# 7seg.net
KiCad netlist of a schematic drawn in EAGLE
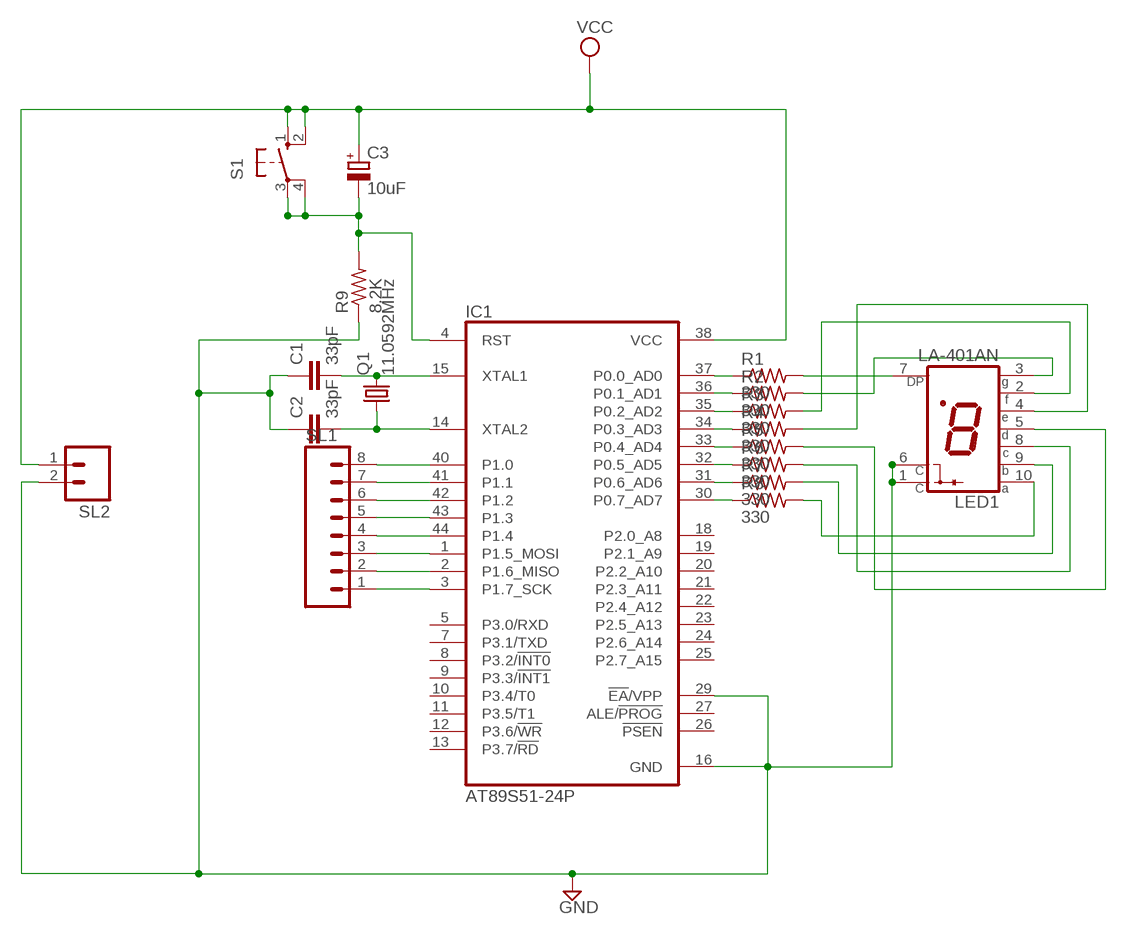
[diagram p0: schematic, sheet 1]

(export (version "E")
  (design (tool "Eeschema 10.0.6"))
  (components
    (comp (ref "C1")
      (value "33pF")
      (footprint "eagle-import:C1206K")
      (libsource (lib "eagle-import") (part "C-EUC1206K"))
    )
    (comp (ref "C2")
      (value "33pF")
      (footprint "eagle-import:C1206K")
      (libsource (lib "eagle-import") (part "C-EUC1206K"))
    )
    (comp (ref "C3")
      (value "10uF")
      (footprint "eagle-import:140CLH-1010")
      (libsource (lib "eagle-import") (part "CPOL-EU140CLH-1010"))
    )
    (comp (ref "IC1")
      (value "AT89S51-24P")
      (footprint "eagle-import:TQFP44")
      (libsource (lib "eagle-import") (part "AT89S51P-24"))
    )
    (comp (ref "LED1")
      (value "LA-401AN")
      (footprint "eagle-import:LA-401")
      (libsource (lib "eagle-import") (part "LA-401NA"))
    )
    (comp (ref "Q1")
      (value "11.0592MHz")
      (footprint "eagle-import:TC26V")
      (libsource (lib "eagle-import") (part "CRYSTALTC26V"))
    )
    (comp (ref "R1")
      (value "330")
      (footprint "eagle-import:M1206")
      (libsource (lib "eagle-import") (part "R-US_M1206"))
    )
    (comp (ref "R2")
      (value "330")
      (footprint "eagle-import:M1206")
      (libsource (lib "eagle-import") (part "R-US_M1206"))
    )
    (comp (ref "R3")
      (value "330")
      (footprint "eagle-import:M1206")
      (libsource (lib "eagle-import") (part "R-US_M1206"))
    )
    (comp (ref "R4")
      (value "330")
      (footprint "eagle-import:M1206")
      (libsource (lib "eagle-import") (part "R-US_M1206"))
    )
    (comp (ref "R5")
      (value "330")
      (footprint "eagle-import:M1206")
      (libsource (lib "eagle-import") (part "R-US_M1206"))
    )
    (comp (ref "R6")
      (value "330")
      (footprint "eagle-import:M1206")
      (libsource (lib "eagle-import") (part "R-US_M1206"))
    )
    (comp (ref "R7")
      (value "330")
      (footprint "eagle-import:M1206")
      (libsource (lib "eagle-import") (part "R-US_M1206"))
    )
    (comp (ref "R8")
      (value "330")
      (footprint "eagle-import:M1206")
      (libsource (lib "eagle-import") (part "R-US_M1206"))
    )
    (comp (ref "R9")
      (value "8.2K")
      (footprint "eagle-import:M1206")
      (libsource (lib "eagle-import") (part "R-US_M1206"))
    )
    (comp (ref "S1")
      (value "10-XX")
      (footprint "eagle-import:B3F-10XX")
      (fields (field (name "MPN") "B3F-1000"))
      (libsource (lib "eagle-import") (part "10-XX"))
    )
    (comp (ref "SL1")
      (value "MA08")
      (footprint "eagle-import:08PA")
      (libsource (lib "eagle-import") (part "MA08"))
    )
    (comp (ref "SL2")
      (value "MA02")
      (footprint "eagle-import:02PA")
      (libsource (lib "eagle-import") (part "MA02"))
    )
  )
  (nets
    (net (code "1") (name "GND") (class "Default")
      (node (ref "C1") (pin "1") (pinfunction "1_1") (pintype "passive"))
      (node (ref "C2") (pin "1") (pinfunction "1_1") (pintype "passive"))
      (node (ref "IC1") (pin "16") (pinfunction "GND_16") (pintype "power_in"))
      (node (ref "IC1") (pin "29") (pinfunction "~{EA}/VPP_29") (pintype "input"))
      (node (ref "LED1") (pin "1") (pinfunction "C_1") (pintype "passive"))
      (node (ref "LED1") (pin "6") (pinfunction "C_6") (pintype "passive"))
      (node (ref "R9") (pin "1") (pinfunction "1_1") (pintype "passive"))
      (node (ref "SL2") (pin "2") (pinfunction "2_2") (pintype "passive"))
    )
    (net (code "2") (name "Net-(IC1A-P0.0_AD0)") (class "Default")
      (node (ref "IC1") (pin "37") (pinfunction "P0.0_AD0_37") (pintype "bidirectional"))
      (node (ref "R1") (pin "1") (pinfunction "1_1") (pintype "passive"))
    )
    (net (code "3") (name "Net-(IC1A-P0.1_AD1)") (class "Default")
      (node (ref "IC1") (pin "36") (pinfunction "P0.1_AD1_36") (pintype "bidirectional"))
      (node (ref "R2") (pin "1") (pinfunction "1_1") (pintype "passive"))
    )
    (net (code "4") (name "Net-(IC1A-P0.2_AD2)") (class "Default")
      (node (ref "IC1") (pin "35") (pinfunction "P0.2_AD2_35") (pintype "bidirectional"))
      (node (ref "R3") (pin "1") (pinfunction "1_1") (pintype "passive"))
    )
    (net (code "5") (name "Net-(IC1A-P0.3_AD3)") (class "Default")
      (node (ref "IC1") (pin "34") (pinfunction "P0.3_AD3_34") (pintype "bidirectional"))
      (node (ref "R4") (pin "1") (pinfunction "1_1") (pintype "passive"))
    )
    (net (code "6") (name "Net-(IC1A-P0.4_AD4)") (class "Default")
      (node (ref "IC1") (pin "33") (pinfunction "P0.4_AD4_33") (pintype "bidirectional"))
      (node (ref "R5") (pin "1") (pinfunction "1_1") (pintype "passive"))
    )
    (net (code "7") (name "Net-(IC1A-P0.5_AD5)") (class "Default")
      (node (ref "IC1") (pin "32") (pinfunction "P0.5_AD5_32") (pintype "bidirectional"))
      (node (ref "R6") (pin "1") (pinfunction "1_1") (pintype "passive"))
    )
    (net (code "8") (name "Net-(IC1A-P0.6_AD6)") (class "Default")
      (node (ref "IC1") (pin "31") (pinfunction "P0.6_AD6_31") (pintype "bidirectional"))
      (node (ref "R7") (pin "1") (pinfunction "1_1") (pintype "passive"))
    )
    (net (code "9") (name "Net-(IC1A-P0.7_AD7)") (class "Default")
      (node (ref "IC1") (pin "30") (pinfunction "P0.7_AD7_30") (pintype "bidirectional"))
      (node (ref "R8") (pin "1") (pinfunction "1_1") (pintype "passive"))
    )
    (net (code "10") (name "Net-(IC1A-P1.0)") (class "Default")
      (node (ref "IC1") (pin "40") (pinfunction "P1.0_40") (pintype "bidirectional"))
      (node (ref "SL1") (pin "8") (pinfunction "8_8") (pintype "passive"))
    )
    (net (code "11") (name "Net-(IC1A-P1.1)") (class "Default")
      (node (ref "IC1") (pin "41") (pinfunction "P1.1_41") (pintype "bidirectional"))
      (node (ref "SL1") (pin "7") (pinfunction "7_7") (pintype "passive"))
    )
    (net (code "12") (name "Net-(IC1A-P1.2)") (class "Default")
      (node (ref "IC1") (pin "42") (pinfunction "P1.2_42") (pintype "bidirectional"))
      (node (ref "SL1") (pin "6") (pinfunction "6_6") (pintype "passive"))
    )
    (net (code "13") (name "Net-(IC1A-P1.3)") (class "Default")
      (node (ref "IC1") (pin "43") (pinfunction "P1.3_43") (pintype "bidirectional"))
      (node (ref "SL1") (pin "5") (pinfunction "5_5") (pintype "passive"))
    )
    (net (code "14") (name "Net-(IC1A-P1.4)") (class "Default")
      (node (ref "IC1") (pin "44") (pinfunction "P1.4_44") (pintype "bidirectional"))
      (node (ref "SL1") (pin "4") (pinfunction "4_4") (pintype "passive"))
    )
    (net (code "15") (name "Net-(IC1A-P1.5_MOSI)") (class "Default")
      (node (ref "IC1") (pin "1") (pinfunction "P1.5_MOSI_1") (pintype "bidirectional"))
      (node (ref "SL1") (pin "3") (pinfunction "3_3") (pintype "passive"))
    )
    (net (code "16") (name "Net-(IC1A-P1.6_MISO)") (class "Default")
      (node (ref "IC1") (pin "2") (pinfunction "P1.6_MISO_2") (pintype "bidirectional"))
      (node (ref "SL1") (pin "2") (pinfunction "2_2") (pintype "passive"))
    )
    (net (code "17") (name "Net-(IC1A-P1.7_SCK)") (class "Default")
      (node (ref "IC1") (pin "3") (pinfunction "P1.7_SCK_3") (pintype "bidirectional"))
      (node (ref "SL1") (pin "1") (pinfunction "1_1") (pintype "passive"))
    )
    (net (code "18") (name "Net-(IC1A-RST)") (class "Default")
      (node (ref "C3") (pin "-") (pinfunction "-_-") (pintype "passive"))
      (node (ref "IC1") (pin "4") (pinfunction "RST_4") (pintype "input"))
      (node (ref "R9") (pin "2") (pinfunction "2_2") (pintype "passive"))
      (node (ref "S1") (pin "3") (pinfunction "P_3") (pintype "passive"))
      (node (ref "S1") (pin "4") (pinfunction "P1_4") (pintype "passive"))
    )
    (net (code "19") (name "Net-(IC1A-XTAL1)") (class "Default")
      (node (ref "C1") (pin "2") (pinfunction "2_2") (pintype "passive"))
      (node (ref "IC1") (pin "15") (pinfunction "XTAL1_15") (pintype "input"))
      (node (ref "Q1") (pin "2") (pinfunction "2_2") (pintype "passive"))
    )
    (net (code "20") (name "Net-(IC1A-XTAL2)") (class "Default")
      (node (ref "C2") (pin "2") (pinfunction "2_2") (pintype "passive"))
      (node (ref "IC1") (pin "14") (pinfunction "XTAL2_14") (pintype "input"))
      (node (ref "Q1") (pin "1") (pinfunction "1_1") (pintype "passive"))
    )
    (net (code "21") (name "Net-(LED1-A)") (class "Default")
      (node (ref "LED1") (pin "10") (pinfunction "A_10") (pintype "passive"))
      (node (ref "R8") (pin "2") (pinfunction "2_2") (pintype "passive"))
    )
    (net (code "22") (name "Net-(LED1-B)") (class "Default")
      (node (ref "LED1") (pin "9") (pinfunction "B_9") (pintype "passive"))
      (node (ref "R7") (pin "2") (pinfunction "2_2") (pintype "passive"))
    )
    (net (code "23") (name "Net-(LED1-C-Pad8)") (class "Default")
      (node (ref "LED1") (pin "8") (pinfunction "C_8") (pintype "passive"))
      (node (ref "R6") (pin "2") (pinfunction "2_2") (pintype "passive"))
    )
    (net (code "24") (name "Net-(LED1-D)") (class "Default")
      (node (ref "LED1") (pin "5") (pinfunction "D_5") (pintype "passive"))
      (node (ref "R5") (pin "2") (pinfunction "2_2") (pintype "passive"))
    )
    (net (code "25") (name "Net-(LED1-DP)") (class "Default")
      (node (ref "LED1") (pin "7") (pinfunction "DP_7") (pintype "passive"))
      (node (ref "R1") (pin "2") (pinfunction "2_2") (pintype "passive"))
    )
    (net (code "26") (name "Net-(LED1-E)") (class "Default")
      (node (ref "LED1") (pin "4") (pinfunction "E_4") (pintype "passive"))
      (node (ref "R4") (pin "2") (pinfunction "2_2") (pintype "passive"))
    )
    (net (code "27") (name "Net-(LED1-F)") (class "Default")
      (node (ref "LED1") (pin "2") (pinfunction "F_2") (pintype "passive"))
      (node (ref "R3") (pin "2") (pinfunction "2_2") (pintype "passive"))
    )
    (net (code "28") (name "Net-(LED1-G)") (class "Default")
      (node (ref "LED1") (pin "3") (pinfunction "G_3") (pintype "passive"))
      (node (ref "R2") (pin "2") (pinfunction "2_2") (pintype "passive"))
    )
    (net (code "29") (name "VCC") (class "Default")
      (node (ref "C3") (pin "+") (pinfunction "+_+") (pintype "passive"))
      (node (ref "IC1") (pin "38") (pinfunction "VCC_38") (pintype "power_in"))
      (node (ref "S1") (pin "1") (pinfunction "S_1") (pintype "passive"))
      (node (ref "S1") (pin "2") (pinfunction "S1_2") (pintype "passive"))
      (node (ref "SL2") (pin "1") (pinfunction "1_1") (pintype "passive"))
    )
    (net (code "30") (name "unconnected-(IC1A-ALE{slash}~{PROG}-Pad27)") (class "Default")
      (node (ref "IC1") (pin "27") (pinfunction "ALE/~{PROG}_27") (pintype "output"))
    )
    (net (code "31") (name "unconnected-(IC1A-P2.0_A8-Pad18)") (class "Default")
      (node (ref "IC1") (pin "18") (pinfunction "P2.0_A8_18") (pintype "bidirectional"))
    )
    (net (code "32") (name "unconnected-(IC1A-P2.1_A9-Pad19)") (class "Default")
      (node (ref "IC1") (pin "19") (pinfunction "P2.1_A9_19") (pintype "bidirectional"))
    )
    (net (code "33") (name "unconnected-(IC1A-P2.2_A10-Pad20)") (class "Default")
      (node (ref "IC1") (pin "20") (pinfunction "P2.2_A10_20") (pintype "bidirectional"))
    )
    (net (code "34") (name "unconnected-(IC1A-P2.3_A11-Pad21)") (class "Default")
      (node (ref "IC1") (pin "21") (pinfunction "P2.3_A11_21") (pintype "bidirectional"))
    )
    (net (code "35") (name "unconnected-(IC1A-P2.4_A12-Pad22)") (class "Default")
      (node (ref "IC1") (pin "22") (pinfunction "P2.4_A12_22") (pintype "bidirectional"))
    )
    (net (code "36") (name "unconnected-(IC1A-P2.5_A13-Pad23)") (class "Default")
      (node (ref "IC1") (pin "23") (pinfunction "P2.5_A13_23") (pintype "bidirectional"))
    )
    (net (code "37") (name "unconnected-(IC1A-P2.6_A14-Pad24)") (class "Default")
      (node (ref "IC1") (pin "24") (pinfunction "P2.6_A14_24") (pintype "bidirectional"))
    )
    (net (code "38") (name "unconnected-(IC1A-P2.7_A15-Pad25)") (class "Default")
      (node (ref "IC1") (pin "25") (pinfunction "P2.7_A15_25") (pintype "bidirectional"))
    )
    (net (code "39") (name "unconnected-(IC1A-P3.0{slash}RXD-Pad5)") (class "Default")
      (node (ref "IC1") (pin "5") (pinfunction "P3.0/RXD_5") (pintype "bidirectional"))
    )
    (net (code "40") (name "unconnected-(IC1A-P3.1{slash}TXD-Pad7)") (class "Default")
      (node (ref "IC1") (pin "7") (pinfunction "P3.1/TXD_7") (pintype "bidirectional"))
    )
    (net (code "41") (name "unconnected-(IC1A-P3.2{slash}~{INT0}-Pad8)") (class "Default")
      (node (ref "IC1") (pin "8") (pinfunction "P3.2/~{INT0}_8") (pintype "bidirectional"))
    )
    (net (code "42") (name "unconnected-(IC1A-P3.3{slash}~{INT1}-Pad9)") (class "Default")
      (node (ref "IC1") (pin "9") (pinfunction "P3.3/~{INT1}_9") (pintype "bidirectional"))
    )
    (net (code "43") (name "unconnected-(IC1A-P3.4{slash}T0-Pad10)") (class "Default")
      (node (ref "IC1") (pin "10") (pinfunction "P3.4/T0_10") (pintype "bidirectional"))
    )
    (net (code "44") (name "unconnected-(IC1A-P3.5{slash}T1-Pad11)") (class "Default")
      (node (ref "IC1") (pin "11") (pinfunction "P3.5/T1_11") (pintype "bidirectional"))
    )
    (net (code "45") (name "unconnected-(IC1A-P3.6{slash}~{WR}-Pad12)") (class "Default")
      (node (ref "IC1") (pin "12") (pinfunction "P3.6/~{WR}_12") (pintype "bidirectional"))
    )
    (net (code "46") (name "unconnected-(IC1A-P3.7{slash}~{RD}-Pad13)") (class "Default")
      (node (ref "IC1") (pin "13") (pinfunction "P3.7/~{RD}_13") (pintype "bidirectional"))
    )
    (net (code "47") (name "unconnected-(IC1A-~{PSEN}-Pad26)") (class "Default")
      (node (ref "IC1") (pin "26") (pinfunction "~{PSEN}_26") (pintype "output"))
    )
  )
)
